# mcu.net
KiCad netlist of a schematic drawn in Altium Designer
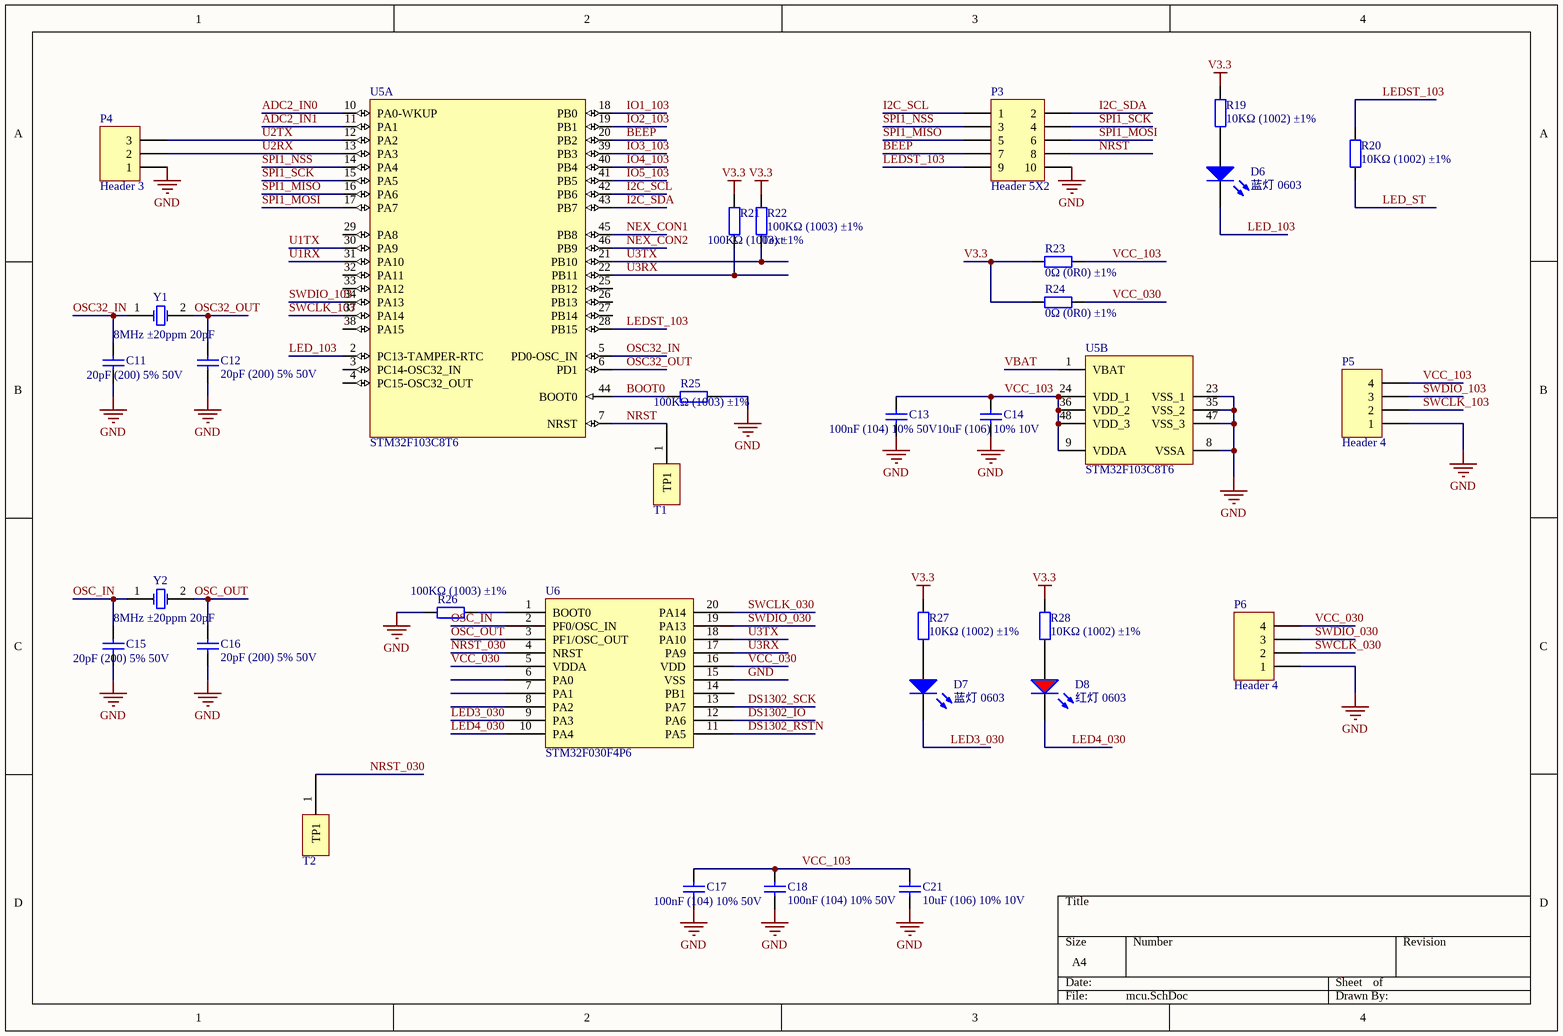
[diagram p0: mcu.SchDoc]

(export (version "E")
  (design (tool "Eeschema 10.0.6"))
  (components
    (comp (ref "C11")
      (value "20pF (200) 5% 50V")
      (footprint "0603_C")
      (description "贴片电容")
      (libsource (lib "Miscellaneous Devices LC") (part "0603 20pF (200) 5% 50V"))
    )
    (comp (ref "C12")
      (value "20pF (200) 5% 50V")
      (footprint "0603_C")
      (description "贴片电容")
      (libsource (lib "Miscellaneous Devices LC") (part "0603 20pF (200) 5% 50V"))
    )
    (comp (ref "C13")
      (value "100nF (104) 10% 50V")
      (footprint "0603_C")
      (description "贴片电容")
      (libsource (lib "Miscellaneous Devices LC") (part "0603 100nF (104) 10% 50V"))
    )
    (comp (ref "C14")
      (value "10uF (106) 10% 10V")
      (footprint "0603_C")
      (description "贴片电容")
      (libsource (lib "Miscellaneous Devices LC") (part "0603 10uF (106) 10% 10V"))
    )
    (comp (ref "C15")
      (value "20pF (200) 5% 50V")
      (footprint "0603_C")
      (description "贴片电容")
      (libsource (lib "Miscellaneous Devices LC") (part "0603 20pF (200) 5% 50V"))
    )
    (comp (ref "C16")
      (value "20pF (200) 5% 50V")
      (footprint "0603_C")
      (description "贴片电容")
      (libsource (lib "Miscellaneous Devices LC") (part "0603 20pF (200) 5% 50V"))
    )
    (comp (ref "C17")
      (value "100nF (104) 10% 50V")
      (footprint "1206_C")
      (description "贴片电容")
      (libsource (lib "Miscellaneous Devices LC") (part "1206 100nF (104) 10% 50V"))
    )
    (comp (ref "C18")
      (value "100nF (104) 10% 50V")
      (footprint "1206_C")
      (description "贴片电容")
      (libsource (lib "Miscellaneous Devices LC") (part "1206 100nF (104) 10% 50V"))
    )
    (comp (ref "C21")
      (value "10uF (106) 10% 10V")
      (footprint "0603_C")
      (description "贴片电容")
      (libsource (lib "Miscellaneous Devices LC") (part "0603 10uF (106) 10% 10V"))
    )
    (comp (ref "D6")
      (value "蓝灯 0603")
      (footprint "0603_LED_S1")
      (description "发光二极管")
      (libsource (lib "Miscellaneous Devices LC") (part "0603 蓝灯"))
    )
    (comp (ref "D7")
      (value "蓝灯 0603")
      (footprint "0603_LED_S1")
      (description "发光二极管")
      (libsource (lib "Miscellaneous Devices LC") (part "0603 蓝灯"))
    )
    (comp (ref "D8")
      (value "红灯 0603")
      (footprint "0603_LED_S1")
      (description "发光二极管")
      (libsource (lib "Miscellaneous Devices LC") (part "0603 红灯"))
    )
    (comp (ref "P3")
      (value "Header 5X2")
      (footprint "HDR2X5")
      (description "Header, 5-Pin, Dual row")
      (fields (field (name "PUBLISHER") "Altium Limited"))
      (libsource (lib "Miscellaneous Connectors") (part "Header 5X2"))
    )
    (comp (ref "P4")
      (value "Header 3")
      (footprint "HDR1X3")
      (description "Header, 3-Pin")
      (fields (field (name "PUBLISHER") "Altium Limited"))
      (libsource (lib "Miscellaneous Connectors") (part "Header 3"))
    )
    (comp (ref "P5")
      (value "Header 4")
      (footprint "HDR1X4")
      (description "Header, 4-Pin")
      (fields (field (name "PUBLISHER") "Altium Limited"))
      (libsource (lib "Miscellaneous Connectors") (part "Header 4"))
    )
    (comp (ref "P6")
      (value "Header 4")
      (footprint "HDR1X4")
      (description "Header, 4-Pin")
      (fields (field (name "PUBLISHER") "Altium Limited"))
      (libsource (lib "Miscellaneous Connectors") (part "Header 4"))
    )
    (comp (ref "R19")
      (value "10KΩ (1002) ±1%")
      (footprint "0603_R")
      (description "贴片电阻")
      (libsource (lib "Miscellaneous Devices LC") (part "0603 10KΩ (1002) 1%"))
    )
    (comp (ref "R20")
      (value "10KΩ (1002) ±1%")
      (footprint "0603_R")
      (description "贴片电阻")
      (libsource (lib "Miscellaneous Devices LC") (part "0603 10KΩ (1002) 1%"))
    )
    (comp (ref "R21")
      (value "100KΩ (1003) ±1%")
      (footprint "0603_R")
      (description "贴片电阻")
      (libsource (lib "") (part "0603 100KΩ (1003) 1%_1"))
    )
    (comp (ref "R22")
      (value "100KΩ (1003) ±1%")
      (footprint "0603_R")
      (description "贴片电阻")
      (libsource (lib "") (part "0603 100KΩ (1003) 1%_1"))
    )
    (comp (ref "R23")
      (value "0Ω (0R0) ±1%")
      (footprint "1206_R")
      (description "贴片电阻")
      (libsource (lib "Miscellaneous Devices LC") (part "1206 0Ω (0R0) 1%"))
    )
    (comp (ref "R24")
      (value "0Ω (0R0) ±1%")
      (footprint "1206_R")
      (description "贴片电阻")
      (libsource (lib "Miscellaneous Devices LC") (part "1206 0Ω (0R0) 1%"))
    )
    (comp (ref "R25")
      (value "100KΩ (1003) ±1%")
      (footprint "0603_R")
      (description "贴片电阻")
      (libsource (lib "Miscellaneous Devices LC") (part "0603 100KΩ (1003) 1%"))
    )
    (comp (ref "R26")
      (value "100KΩ (1003) ±1%")
      (footprint "0603_R")
      (description "贴片电阻")
      (libsource (lib "Miscellaneous Devices LC") (part "0603 100KΩ (1003) 1%"))
    )
    (comp (ref "R27")
      (value "10KΩ (1002) ±1%")
      (footprint "0603_R")
      (description "贴片电阻")
      (libsource (lib "Miscellaneous Devices LC") (part "0603 10KΩ (1002) 1%"))
    )
    (comp (ref "R28")
      (value "10KΩ (1002) ±1%")
      (footprint "0603_R")
      (description "贴片电阻")
      (libsource (lib "Miscellaneous Devices LC") (part "0603 10KΩ (1002) 1%"))
    )
    (comp (ref "T1") (value "TP1") (footprint "TP1") (libsource (lib "CHK-I") (part "TP1")))
    (comp (ref "T2") (value "TP1") (footprint "TP1") (libsource (lib "CHK-I") (part "TP1")))
    (comp (ref "U5")
      (value "STM32F103C8T6")
      (footprint "LQFP-48_7x7x05P")
      (description "ARM")
      (libsource (lib "Miscellaneous Devices LC") (part "STM32F103C8T6"))
    )
    (comp (ref "U6")
      (value "STM32F030F4P6")
      (footprint "TSSOP-20")
      (description "ARM")
      (libsource (lib "Miscellaneous Devices LC") (part "STM32F030F4P6"))
    )
    (comp (ref "Y1")
      (value "8MHz ±20ppm 20pF")
      (footprint "SMD-5032_2P")
      (description "贴片晶振")
      (libsource (lib "Miscellaneous Devices LC") (part "SMD-5032_2P 8MHz 20ppm 20pF"))
    )
    (comp (ref "Y2")
      (value "8MHz ±20ppm 20pF")
      (footprint "SMD-5032_2P")
      (description "贴片晶振")
      (libsource (lib "Miscellaneous Devices LC") (part "SMD-5032_2P 8MHz 20ppm 20pF"))
    )
  )
  (nets
    (net (code "1") (name "/ADC2_IN0") (class "Default")
      (node (ref "U5") (pin "10") (pinfunction "PA0-WKUP_10") (pintype "bidirectional"))
    )
    (net (code "2") (name "/ADC2_IN1") (class "Default")
      (node (ref "U5") (pin "11") (pinfunction "PA1_11") (pintype "bidirectional"))
    )
    (net (code "3") (name "/BEEP") (class "Default")
      (node (ref "P3") (pin "7") (pinfunction "7_7") (pintype "passive"))
      (node (ref "U5") (pin "20") (pinfunction "PB2_20") (pintype "bidirectional"))
    )
    (net (code "4") (name "/BOOT0") (class "Default")
      (node (ref "R25") (pin "1") (pinfunction "1_1") (pintype "passive"))
      (node (ref "U5") (pin "44") (pinfunction "BOOT0_44") (pintype "input"))
    )
    (net (code "5") (name "/DS1302_IO") (class "Default")
      (node (ref "U6") (pin "12") (pinfunction "PA6_12") (pintype "passive"))
    )
    (net (code "6") (name "/DS1302_RSTN") (class "Default")
      (node (ref "U6") (pin "11") (pinfunction "PA5_11") (pintype "passive"))
    )
    (net (code "7") (name "/DS1302_SCK") (class "Default")
      (node (ref "U6") (pin "13") (pinfunction "PA7_13") (pintype "passive"))
    )
    (net (code "8") (name "/I2C_SCL") (class "Default")
      (node (ref "P3") (pin "1") (pinfunction "1_1") (pintype "passive"))
      (node (ref "U5") (pin "42") (pinfunction "PB6_42") (pintype "bidirectional"))
    )
    (net (code "9") (name "/I2C_SDA") (class "Default")
      (node (ref "P3") (pin "2") (pinfunction "2_2") (pintype "passive"))
      (node (ref "U5") (pin "43") (pinfunction "PB7_43") (pintype "bidirectional"))
    )
    (net (code "10") (name "/IO1_103") (class "Default")
      (node (ref "U5") (pin "18") (pinfunction "PB0_18") (pintype "bidirectional"))
    )
    (net (code "11") (name "/IO2_103") (class "Default")
      (node (ref "U5") (pin "19") (pinfunction "PB1_19") (pintype "bidirectional"))
    )
    (net (code "12") (name "/IO3_103") (class "Default")
      (node (ref "U5") (pin "39") (pinfunction "PB3_39") (pintype "bidirectional"))
    )
    (net (code "13") (name "/IO4_103") (class "Default")
      (node (ref "U5") (pin "40") (pinfunction "PB4_40") (pintype "bidirectional"))
    )
    (net (code "14") (name "/IO5_103") (class "Default")
      (node (ref "U5") (pin "41") (pinfunction "PB5_41") (pintype "bidirectional"))
    )
    (net (code "15") (name "/LED3_030") (class "Default")
      (node (ref "D7") (pin "K") (pinfunction "K_K") (pintype "passive"))
      (node (ref "U6") (pin "9") (pinfunction "PA3_9") (pintype "passive"))
    )
    (net (code "16") (name "/LED4_030") (class "Default")
      (node (ref "D8") (pin "K") (pinfunction "K_K") (pintype "passive"))
      (node (ref "U6") (pin "10") (pinfunction "PA4_10") (pintype "passive"))
    )
    (net (code "17") (name "/LEDST_103") (class "Default")
      (node (ref "P3") (pin "9") (pinfunction "9_9") (pintype "passive"))
      (node (ref "R20") (pin "2") (pinfunction "2_2") (pintype "passive"))
      (node (ref "U5") (pin "28") (pinfunction "PB15_28") (pintype "bidirectional"))
    )
    (net (code "18") (name "/LED_103") (class "Default")
      (node (ref "D6") (pin "K") (pinfunction "K_K") (pintype "passive"))
      (node (ref "U5") (pin "2") (pinfunction "PC13-TAMPER-RTC_2") (pintype "bidirectional"))
    )
    (net (code "19") (name "/LED_ST") (class "Default")
      (node (ref "R20") (pin "1") (pinfunction "1_1") (pintype "passive"))
    )
    (net (code "20") (name "/NEX_CON1") (class "Default")
      (node (ref "U5") (pin "45") (pinfunction "PB8_45") (pintype "bidirectional"))
    )
    (net (code "21") (name "/NEX_CON2") (class "Default")
      (node (ref "U5") (pin "46") (pinfunction "PB9_46") (pintype "bidirectional"))
    )
    (net (code "22") (name "/NRST") (class "Default")
      (node (ref "P3") (pin "8") (pinfunction "8_8") (pintype "passive"))
      (node (ref "T1") (pin "1") (pinfunction "TP1_1") (pintype "passive"))
      (node (ref "U5") (pin "7") (pinfunction "NRST_7") (pintype "bidirectional"))
    )
    (net (code "23") (name "/NRST_030") (class "Default")
      (node (ref "T2") (pin "1") (pinfunction "TP1_1") (pintype "passive"))
      (node (ref "U6") (pin "4") (pinfunction "NRST_4") (pintype "passive"))
    )
    (net (code "24") (name "/OSC32_IN") (class "Default")
      (node (ref "C11") (pin "2") (pinfunction "2_2") (pintype "passive"))
      (node (ref "U5") (pin "5") (pinfunction "PD0-OSC_IN_5") (pintype "bidirectional"))
      (node (ref "Y1") (pin "1") (pinfunction "OSC1_1") (pintype "passive"))
    )
    (net (code "25") (name "/OSC32_OUT") (class "Default")
      (node (ref "C12") (pin "2") (pinfunction "2_2") (pintype "passive"))
      (node (ref "U5") (pin "6") (pinfunction "PD1_6") (pintype "bidirectional"))
      (node (ref "Y1") (pin "2") (pinfunction "OSC2_2") (pintype "passive"))
    )
    (net (code "26") (name "/OSC_IN") (class "Default")
      (node (ref "C15") (pin "2") (pinfunction "2_2") (pintype "passive"))
      (node (ref "U6") (pin "2") (pinfunction "PF0/OSC_IN_2") (pintype "passive"))
      (node (ref "Y2") (pin "1") (pinfunction "OSC1_1") (pintype "passive"))
    )
    (net (code "27") (name "/OSC_OUT") (class "Default")
      (node (ref "C16") (pin "2") (pinfunction "2_2") (pintype "passive"))
      (node (ref "U6") (pin "3") (pinfunction "PF1/OSC_OUT_3") (pintype "passive"))
      (node (ref "Y2") (pin "2") (pinfunction "OSC2_2") (pintype "passive"))
    )
    (net (code "28") (name "/SPI1_MISO") (class "Default")
      (node (ref "P3") (pin "5") (pinfunction "5_5") (pintype "passive"))
      (node (ref "U5") (pin "16") (pinfunction "PA6_16") (pintype "bidirectional"))
    )
    (net (code "29") (name "/SPI1_MOSI") (class "Default")
      (node (ref "P3") (pin "6") (pinfunction "6_6") (pintype "passive"))
      (node (ref "U5") (pin "17") (pinfunction "PA7_17") (pintype "bidirectional"))
    )
    (net (code "30") (name "/SPI1_NSS") (class "Default")
      (node (ref "P3") (pin "3") (pinfunction "3_3") (pintype "passive"))
      (node (ref "U5") (pin "14") (pinfunction "PA4_14") (pintype "bidirectional"))
    )
    (net (code "31") (name "/SPI1_SCK") (class "Default")
      (node (ref "P3") (pin "4") (pinfunction "4_4") (pintype "passive"))
      (node (ref "U5") (pin "15") (pinfunction "PA5_15") (pintype "bidirectional"))
    )
    (net (code "32") (name "/SWCLK_030") (class "Default")
      (node (ref "P6") (pin "2") (pinfunction "2_2") (pintype "passive"))
      (node (ref "U6") (pin "20") (pinfunction "PA14_20") (pintype "passive"))
    )
    (net (code "33") (name "/SWCLK_103") (class "Default")
      (node (ref "P5") (pin "2") (pinfunction "2_2") (pintype "passive"))
      (node (ref "U5") (pin "37") (pinfunction "PA14_37") (pintype "bidirectional"))
    )
    (net (code "34") (name "/SWDIO_030") (class "Default")
      (node (ref "P6") (pin "3") (pinfunction "3_3") (pintype "passive"))
      (node (ref "U6") (pin "19") (pinfunction "PA13_19") (pintype "passive"))
    )
    (net (code "35") (name "/SWDIO_103") (class "Default")
      (node (ref "P5") (pin "3") (pinfunction "3_3") (pintype "passive"))
      (node (ref "U5") (pin "34") (pinfunction "PA13_34") (pintype "bidirectional"))
    )
    (net (code "36") (name "/U1RX") (class "Default")
      (node (ref "U5") (pin "31") (pinfunction "PA10_31") (pintype "bidirectional"))
    )
    (net (code "37") (name "/U1TX") (class "Default")
      (node (ref "U5") (pin "30") (pinfunction "PA9_30") (pintype "bidirectional"))
    )
    (net (code "38") (name "/U2RX") (class "Default")
      (node (ref "P4") (pin "2") (pinfunction "2_2") (pintype "passive"))
      (node (ref "U5") (pin "13") (pinfunction "PA3_13") (pintype "bidirectional"))
    )
    (net (code "39") (name "/U2TX") (class "Default")
      (node (ref "P4") (pin "3") (pinfunction "3_3") (pintype "passive"))
      (node (ref "U5") (pin "12") (pinfunction "PA2_12") (pintype "bidirectional"))
    )
    (net (code "40") (name "/U3RX") (class "Default")
      (node (ref "R21") (pin "1") (pinfunction "1_1") (pintype "passive"))
      (node (ref "U5") (pin "22") (pinfunction "PB11_22") (pintype "bidirectional"))
      (node (ref "U6") (pin "17") (pinfunction "PA9_17") (pintype "passive"))
    )
    (net (code "41") (name "/U3TX") (class "Default")
      (node (ref "R22") (pin "1") (pinfunction "1_1") (pintype "passive"))
      (node (ref "U5") (pin "21") (pinfunction "PB10_21") (pintype "bidirectional"))
      (node (ref "U6") (pin "18") (pinfunction "PA10_18") (pintype "passive"))
    )
    (net (code "42") (name "/VBAT") (class "Default")
      (node (ref "U5") (pin "1") (pinfunction "VBAT_1") (pintype "power_in"))
    )
    (net (code "43") (name "/VCC_030") (class "Default")
      (node (ref "P6") (pin "4") (pinfunction "4_4") (pintype "passive"))
      (node (ref "R24") (pin "2") (pinfunction "2_2") (pintype "passive"))
      (node (ref "U6") (pin "16") (pinfunction "VDD_16") (pintype "passive"))
      (node (ref "U6") (pin "5") (pinfunction "VDDA_5") (pintype "passive"))
    )
    (net (code "44") (name "/VCC_103") (class "Default")
      (node (ref "C13") (pin "2") (pinfunction "2_2") (pintype "passive"))
      (node (ref "C14") (pin "1") (pinfunction "1_1") (pintype "passive"))
      (node (ref "C17") (pin "2") (pinfunction "2_2") (pintype "passive"))
      (node (ref "C18") (pin "2") (pinfunction "2_2") (pintype "passive"))
      (node (ref "C21") (pin "1") (pinfunction "1_1") (pintype "passive"))
      (node (ref "P5") (pin "4") (pinfunction "4_4") (pintype "passive"))
      (node (ref "R23") (pin "2") (pinfunction "2_2") (pintype "passive"))
      (node (ref "U5") (pin "24") (pinfunction "VDD_1_24") (pintype "power_in"))
      (node (ref "U5") (pin "36") (pinfunction "VDD_2_36") (pintype "power_in"))
      (node (ref "U5") (pin "48") (pinfunction "VDD_3_48") (pintype "power_in"))
      (node (ref "U5") (pin "9") (pinfunction "VDDA_9") (pintype "power_in"))
    )
    (net (code "45") (name "GND") (class "Default")
      (node (ref "C11") (pin "1") (pinfunction "1_1") (pintype "passive"))
      (node (ref "C12") (pin "1") (pinfunction "1_1") (pintype "passive"))
      (node (ref "C13") (pin "1") (pinfunction "1_1") (pintype "passive"))
      (node (ref "C14") (pin "2") (pinfunction "2_2") (pintype "passive"))
      (node (ref "C15") (pin "1") (pinfunction "1_1") (pintype "passive"))
      (node (ref "C16") (pin "1") (pinfunction "1_1") (pintype "passive"))
      (node (ref "C17") (pin "1") (pinfunction "1_1") (pintype "passive"))
      (node (ref "C18") (pin "1") (pinfunction "1_1") (pintype "passive"))
      (node (ref "C21") (pin "2") (pinfunction "2_2") (pintype "passive"))
      (node (ref "P3") (pin "10") (pinfunction "10_10") (pintype "passive"))
      (node (ref "P4") (pin "1") (pinfunction "1_1") (pintype "passive"))
      (node (ref "P5") (pin "1") (pinfunction "1_1") (pintype "passive"))
      (node (ref "P6") (pin "1") (pinfunction "1_1") (pintype "passive"))
      (node (ref "R25") (pin "2") (pinfunction "2_2") (pintype "passive"))
      (node (ref "R26") (pin "1") (pinfunction "1_1") (pintype "passive"))
      (node (ref "U5") (pin "23") (pinfunction "VSS_1_23") (pintype "power_in"))
      (node (ref "U5") (pin "35") (pinfunction "VSS_2_35") (pintype "power_in"))
      (node (ref "U5") (pin "47") (pinfunction "VSS_3_47") (pintype "power_in"))
      (node (ref "U5") (pin "8") (pinfunction "VSSA_8") (pintype "power_in"))
      (node (ref "U6") (pin "15") (pinfunction "VSS_15") (pintype "passive"))
    )
    (net (code "46") (name "Net-(D6-PadA)") (class "Default")
      (node (ref "D6") (pin "A") (pinfunction "A_A") (pintype "passive"))
      (node (ref "R19") (pin "1") (pinfunction "1_1") (pintype "passive"))
    )
    (net (code "47") (name "Net-(D7-PadA)") (class "Default")
      (node (ref "D7") (pin "A") (pinfunction "A_A") (pintype "passive"))
      (node (ref "R27") (pin "1") (pinfunction "1_1") (pintype "passive"))
    )
    (net (code "48") (name "Net-(D8-PadA)") (class "Default")
      (node (ref "D8") (pin "A") (pinfunction "A_A") (pintype "passive"))
      (node (ref "R28") (pin "1") (pinfunction "1_1") (pintype "passive"))
    )
    (net (code "49") (name "Net-(U6-BOOT0)") (class "Default")
      (node (ref "R26") (pin "2") (pinfunction "2_2") (pintype "passive"))
      (node (ref "U6") (pin "1") (pinfunction "BOOT0_1") (pintype "passive"))
    )
    (net (code "50") (name "V3.3") (class "Default")
      (node (ref "R19") (pin "2") (pinfunction "2_2") (pintype "passive"))
      (node (ref "R21") (pin "2") (pinfunction "2_2") (pintype "passive"))
      (node (ref "R22") (pin "2") (pinfunction "2_2") (pintype "passive"))
      (node (ref "R23") (pin "1") (pinfunction "1_1") (pintype "passive"))
      (node (ref "R24") (pin "1") (pinfunction "1_1") (pintype "passive"))
      (node (ref "R27") (pin "2") (pinfunction "2_2") (pintype "passive"))
      (node (ref "R28") (pin "2") (pinfunction "2_2") (pintype "passive"))
    )
    (net (code "51") (name "unconnected-(U5A-PA8-Pad29)") (class "Default")
      (node (ref "U5") (pin "29") (pinfunction "PA8_29") (pintype "bidirectional"))
    )
    (net (code "52") (name "unconnected-(U5A-PA11-Pad32)") (class "Default")
      (node (ref "U5") (pin "32") (pinfunction "PA11_32") (pintype "bidirectional"))
    )
    (net (code "53") (name "unconnected-(U5A-PA12-Pad33)") (class "Default")
      (node (ref "U5") (pin "33") (pinfunction "PA12_33") (pintype "bidirectional"))
    )
    (net (code "54") (name "unconnected-(U5A-PA15-Pad38)") (class "Default")
      (node (ref "U5") (pin "38") (pinfunction "PA15_38") (pintype "bidirectional"))
    )
    (net (code "55") (name "unconnected-(U5A-PB12-Pad25)") (class "Default")
      (node (ref "U5") (pin "25") (pinfunction "PB12_25") (pintype "bidirectional"))
    )
    (net (code "56") (name "unconnected-(U5A-PB13-Pad26)") (class "Default")
      (node (ref "U5") (pin "26") (pinfunction "PB13_26") (pintype "bidirectional"))
    )
    (net (code "57") (name "unconnected-(U5A-PB14-Pad27)") (class "Default")
      (node (ref "U5") (pin "27") (pinfunction "PB14_27") (pintype "bidirectional"))
    )
    (net (code "58") (name "unconnected-(U5A-PC14-OSC32_IN-Pad3)") (class "Default")
      (node (ref "U5") (pin "3") (pinfunction "PC14-OSC32_IN_3") (pintype "bidirectional"))
    )
    (net (code "59") (name "unconnected-(U5A-PC15-OSC32_OUT-Pad4)") (class "Default")
      (node (ref "U5") (pin "4") (pinfunction "PC15-OSC32_OUT_4") (pintype "bidirectional"))
    )
    (net (code "60") (name "unconnected-(U6-PA0-Pad6)") (class "Default")
      (node (ref "U6") (pin "6") (pinfunction "PA0_6") (pintype "passive"))
    )
    (net (code "61") (name "unconnected-(U6-PA1-Pad7)") (class "Default")
      (node (ref "U6") (pin "7") (pinfunction "PA1_7") (pintype "passive"))
    )
    (net (code "62") (name "unconnected-(U6-PA2-Pad8)") (class "Default")
      (node (ref "U6") (pin "8") (pinfunction "PA2_8") (pintype "passive"))
    )
    (net (code "63") (name "unconnected-(U6-PB1-Pad14)") (class "Default")
      (node (ref "U6") (pin "14") (pinfunction "PB1_14") (pintype "passive"))
    )
  )
)
